# 24V_Rail.net
KiCad netlist of a schematic drawn in Altium Designer
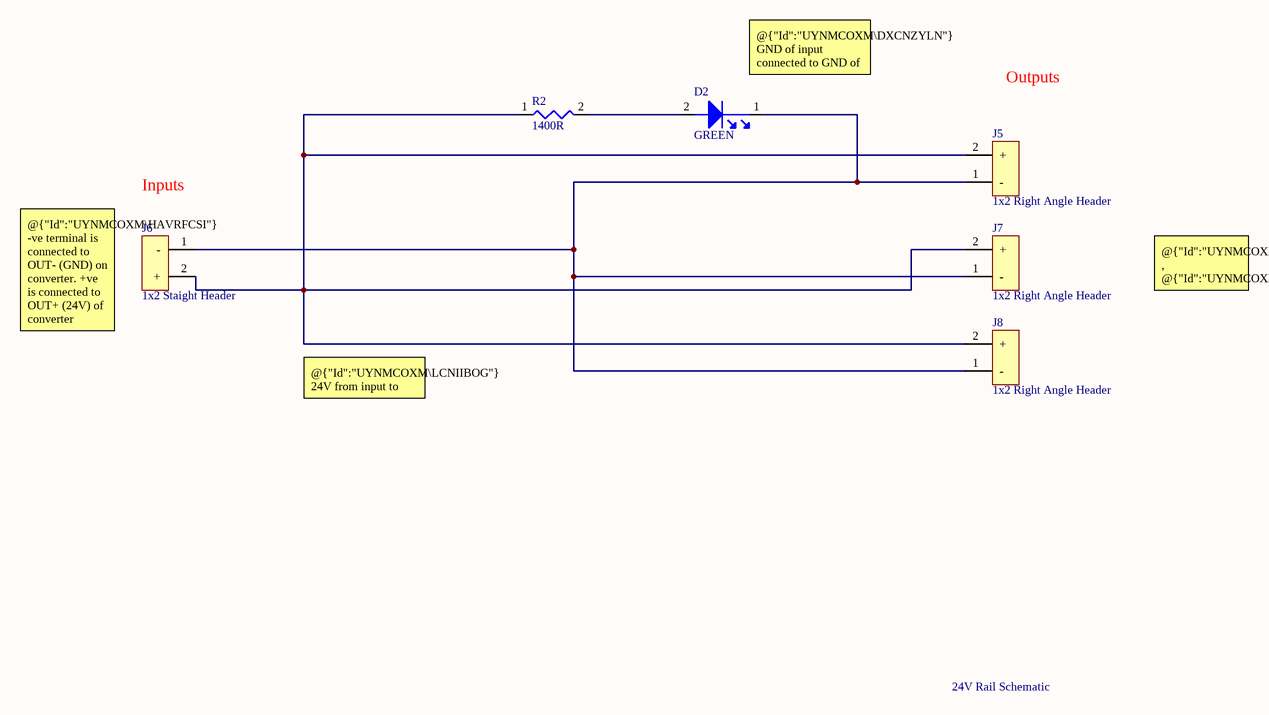
[diagram p0: 24V Rail.SchDoc]

(export (version "E")
  (design (tool "Eeschema 10.0.6"))
  (components
    (comp (ref "D2")
      (value "GREEN")
      (footprint "LED")
      (description "Green T-1 3/4 5 mm 20° Tinted 80 mcd 2.2 V Solid State LED Lamp Through Hole")
      (fields (field (name "MANUFACTURER") "Kingbright") (field (name "MANUFACTURER PART NUMBER") "WP7113GT"))
      (libsource (lib "VR Interface SchLib") (part "WP7113GT"))
    )
    (comp (ref "J5")
      (value "1x2 Right Angle Header")
      (footprint "39291028 Molex Output")
      (description "Connector Wire to Board Header 2 Position 4.2mm Solder Right Angle Thru-Hole Tray")
      (fields (field (name "MANUFACTURER") "Molex") (field (name "MANUFACTURER PART NUMBER") "39-29-1028"))
      (libsource (lib "VR Interface SchLib") (part "39-29-1028"))
    )
    (comp (ref "J6")
      (value "1x2 Staight Header")
      (footprint "39281023 Molex Input")
      (description "Connector Wire to Board Header 2 Position 4.2mm Solder Straight Thru-Hole Tray")
      (fields (field (name "MANUFACTURER") "Molex") (field (name "MANUFACTURER PART NUMBER") "39-28-1023"))
      (libsource (lib "VR Interface SchLib") (part "39-28-1023"))
    )
    (comp (ref "J7")
      (value "1x2 Right Angle Header")
      (footprint "39291028 Molex Output")
      (description "Connector Wire to Board Header 2 Position 4.2mm Solder Right Angle Thru-Hole Tray")
      (fields (field (name "MANUFACTURER") "Molex") (field (name "MANUFACTURER PART NUMBER") "39-29-1028"))
      (libsource (lib "VR Interface SchLib") (part "39-29-1028"))
    )
    (comp (ref "J8")
      (value "1x2 Right Angle Header")
      (footprint "39291028 Molex Output")
      (description "Connector Wire to Board Header 2 Position 4.2mm Solder Right Angle Thru-Hole Tray")
      (fields (field (name "MANUFACTURER") "Molex") (field (name "MANUFACTURER PART NUMBER") "39-29-1028"))
      (libsource (lib "VR Interface SchLib") (part "39-29-1028"))
    )
    (comp (ref "R2")
      (value "1400R")
      (footprint "1400R")
      (description "Res Metal Film 1.4K Ohm 1% 2/5W ±100ppm/°C Conformal AXL Thru-Hole T/R")
      (fields
        (field (name "MANUFACTURER") "Vishay BCcomponents")
        (field (name "MANUFACTURER PART NUMBER") "SFR2500001401FR500")
      )
      (libsource (lib "VR Interface SchLib") (part "SFR2500001401FR500"))
    )
  )
  (nets
    (net (code "1") (name "Net-(D2-Pad2)") (class "Default")
      (node (ref "D2") (pin "2") (pinfunction "2_2") (pintype "passive"))
      (node (ref "R2") (pin "2") (pinfunction "2_2") (pintype "passive"))
    )
    (net (code "2") (name "Net-(J5-+)") (class "Default")
      (node (ref "J5") (pin "2") (pinfunction "+_2") (pintype "passive"))
      (node (ref "J6") (pin "2") (pinfunction "+_2") (pintype "passive"))
      (node (ref "J7") (pin "2") (pinfunction "+_2") (pintype "passive"))
      (node (ref "J8") (pin "2") (pinfunction "+_2") (pintype "passive"))
      (node (ref "R2") (pin "1") (pinfunction "1_1") (pintype "passive"))
    )
    (net (code "3") (name "Net-(J5--)") (class "Default")
      (node (ref "D2") (pin "1") (pinfunction "1_1") (pintype "passive"))
      (node (ref "J5") (pin "1") (pinfunction "-_1") (pintype "passive"))
      (node (ref "J6") (pin "1") (pinfunction "-_1") (pintype "passive"))
      (node (ref "J7") (pin "1") (pinfunction "-_1") (pintype "passive"))
      (node (ref "J8") (pin "1") (pinfunction "-_1") (pintype "passive"))
    )
  )
)
